# ADCMP.net
KiCad netlist of a schematic drawn in Altium Designer
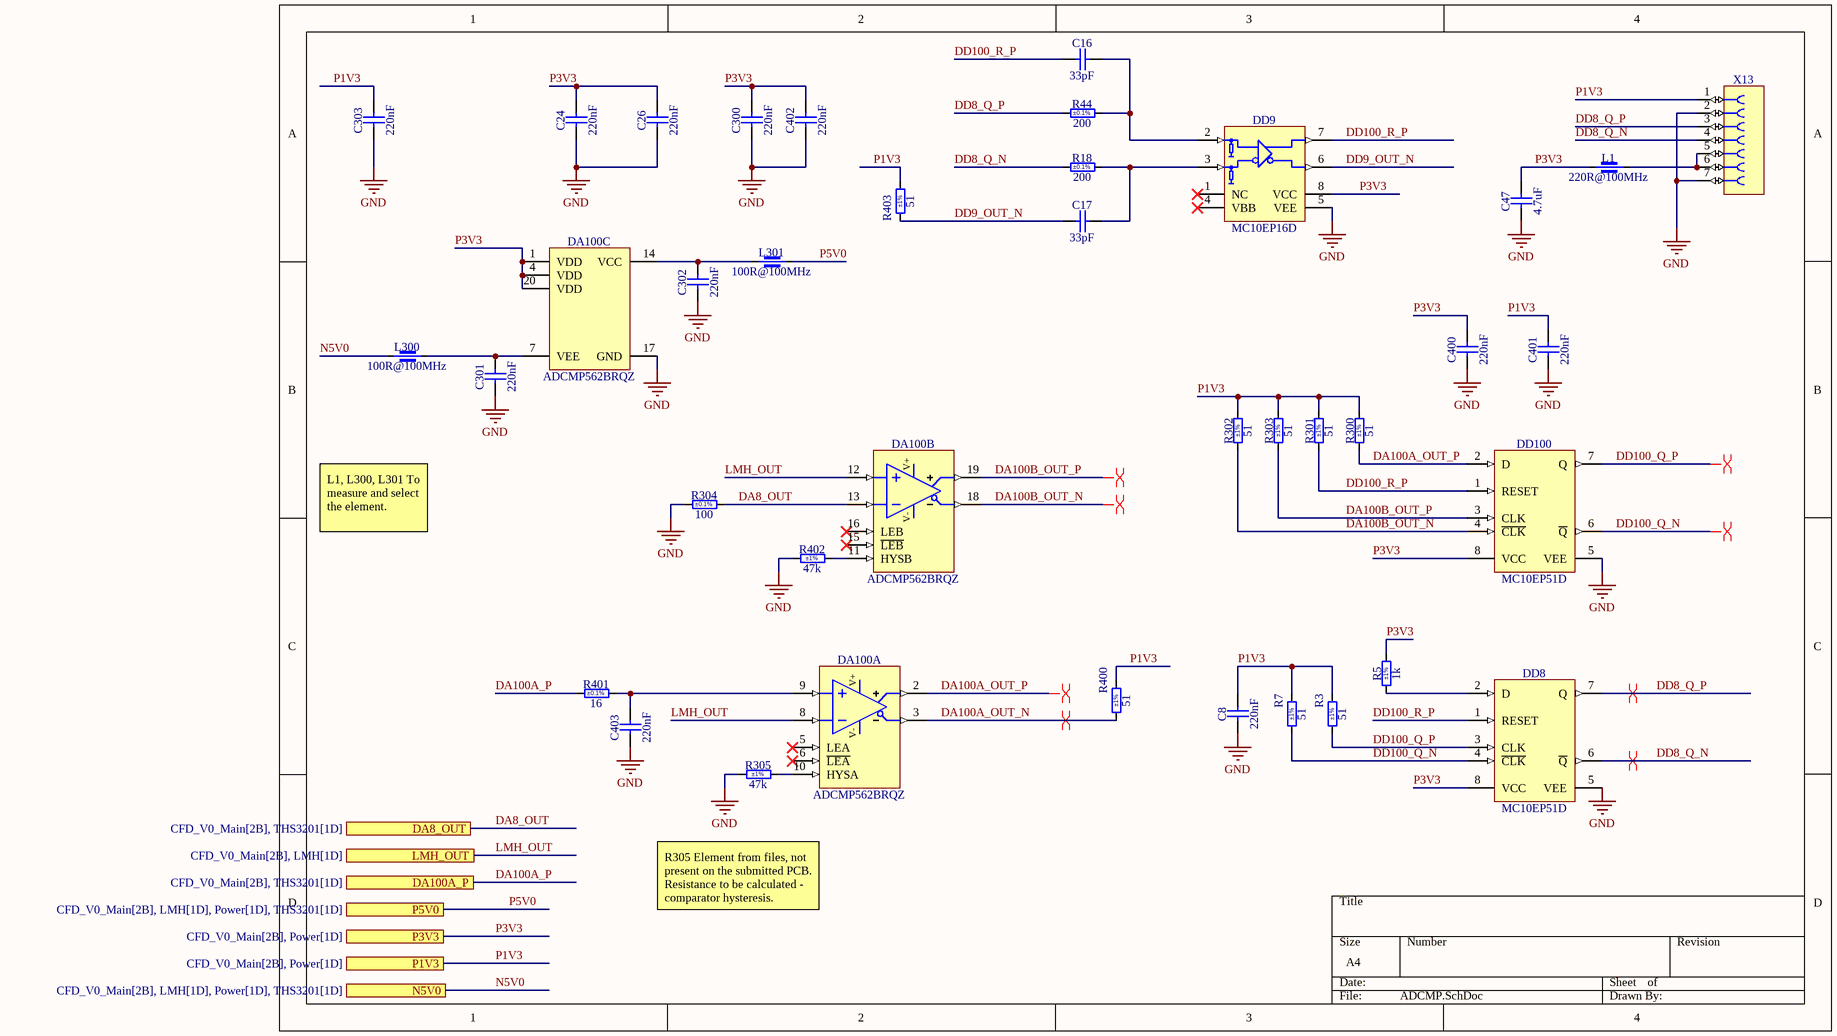
[diagram p0: ADCMP.SchDoc]

(export (version "E")
  (design (tool "Eeschema 10.0.6"))
  (components
    (comp (ref "C8")
      (value "220nF")
      (footprint "CAPC2012X135N")
      (description "Non-polarised capacitor")
      (fields
        (field (name "PART NUMBER") "CC0805_220NF_50V_10%_X7R")
        (field (name "VOLTAGE") "50V")
        (field (name "AUTHOR") "CERN DEM JLC")
      )
      (libsource (lib "Capacitors") (part "Capacitor - non polarized"))
    )
    (comp (ref "C16")
      (value "33pF")
      (footprint "CAPC2012X135N")
      (description "Non-polarised capacitor")
      (fields
        (field (name "PART NUMBER") "CC0805_33PF_50V_5%_NP0")
        (field (name "VOLTAGE") "50V")
        (field (name "AUTHOR") "CERN DEM JLC")
      )
      (libsource (lib "Capacitors") (part "Capacitor - non polarized"))
    )
    (comp (ref "C17")
      (value "33pF")
      (footprint "CAPC2012X135N")
      (description "Non-polarised capacitor")
      (fields
        (field (name "PART NUMBER") "CC0805_33PF_50V_5%_NP0")
        (field (name "VOLTAGE") "50V")
        (field (name "AUTHOR") "CERN DEM JLC")
      )
      (libsource (lib "Capacitors") (part "Capacitor - non polarized"))
    )
    (comp (ref "C24")
      (value "220nF")
      (footprint "CAPC2012X135N")
      (description "Non-polarised capacitor")
      (fields
        (field (name "PART NUMBER") "CC0805_220NF_50V_10%_X7R")
        (field (name "VOLTAGE") "50V")
        (field (name "AUTHOR") "CERN DEM JLC")
      )
      (libsource (lib "Capacitors") (part "Capacitor - non polarized"))
    )
    (comp (ref "C26")
      (value "220nF")
      (footprint "CAPC2012X135N")
      (description "Non-polarised capacitor")
      (fields
        (field (name "PART NUMBER") "CC0805_220NF_50V_10%_X7R")
        (field (name "VOLTAGE") "50V")
        (field (name "AUTHOR") "CERN DEM JLC")
      )
      (libsource (lib "Capacitors") (part "Capacitor - non polarized"))
    )
    (comp (ref "C47")
      (value "4.7uF")
      (footprint "CAPC3216X180N")
      (description "Non-polarised capacitor")
      (fields
        (field (name "PART NUMBER") "CC1206_4.7UF_25V_10%_X7R")
        (field (name "VOLTAGE") "25V")
        (field (name "AUTHOR") "CERN DEM WB")
      )
      (libsource (lib "Capacitors") (part "Capacitor - non polarized"))
    )
    (comp (ref "C300")
      (value "220nF")
      (footprint "CAPC1608X87N")
      (description "Non-polarised capacitor")
      (fields
        (field (name "PART NUMBER") "CC0603_220NF_25V_10%_X7R")
        (field (name "VOLTAGE") "25V")
        (field (name "AUTHOR") "CERN DEM JLC")
      )
      (libsource (lib "Capacitors") (part "Capacitor - non polarized"))
    )
    (comp (ref "C301")
      (value "220nF")
      (footprint "CAPC1608X87N")
      (description "Non-polarised capacitor")
      (fields
        (field (name "PART NUMBER") "CC0603_220NF_25V_10%_X7R")
        (field (name "VOLTAGE") "25V")
        (field (name "AUTHOR") "CERN DEM JLC")
      )
      (libsource (lib "Capacitors") (part "Capacitor - non polarized"))
    )
    (comp (ref "C302")
      (value "220nF")
      (footprint "CAPC1608X87N")
      (description "Non-polarised capacitor")
      (fields
        (field (name "PART NUMBER") "CC0603_220NF_25V_10%_X7R")
        (field (name "VOLTAGE") "25V")
        (field (name "AUTHOR") "CERN DEM JLC")
      )
      (libsource (lib "Capacitors") (part "Capacitor - non polarized"))
    )
    (comp (ref "C303")
      (value "220nF")
      (footprint "CAPC2012X135N")
      (description "Non-polarised capacitor")
      (fields
        (field (name "PART NUMBER") "CC0805_220NF_50V_10%_X7R")
        (field (name "VOLTAGE") "50V")
        (field (name "AUTHOR") "CERN DEM JLC")
      )
      (libsource (lib "Capacitors") (part "Capacitor - non polarized"))
    )
    (comp (ref "C400")
      (value "220nF")
      (footprint "CAPC2012X135N")
      (description "Non-polarised capacitor")
      (fields
        (field (name "PART NUMBER") "CC0805_220NF_50V_10%_X7R")
        (field (name "VOLTAGE") "50V")
        (field (name "AUTHOR") "CERN DEM JLC")
      )
      (libsource (lib "Capacitors") (part "Capacitor - non polarized"))
    )
    (comp (ref "C401")
      (value "220nF")
      (footprint "CAPC2012X135N")
      (description "Non-polarised capacitor")
      (fields
        (field (name "PART NUMBER") "CC0805_220NF_50V_10%_X7R")
        (field (name "VOLTAGE") "50V")
        (field (name "AUTHOR") "CERN DEM JLC")
      )
      (libsource (lib "Capacitors") (part "Capacitor - non polarized"))
    )
    (comp (ref "C402")
      (value "220nF")
      (footprint "CAPC1608X87N")
      (description "Non-polarised capacitor")
      (fields
        (field (name "PART NUMBER") "CC0603_220NF_25V_10%_X7R")
        (field (name "VOLTAGE") "25V")
        (field (name "AUTHOR") "CERN DEM JLC")
      )
      (libsource (lib "Capacitors") (part "Capacitor - non polarized"))
    )
    (comp (ref "C403")
      (value "220nF")
      (footprint "CAPC1608X87N")
      (description "Non-polarised capacitor")
      (fields
        (field (name "PART NUMBER") "CC0603_220NF_25V_10%_X7R")
        (field (name "VOLTAGE") "25V")
        (field (name "AUTHOR") "CERN DEM JLC")
      )
      (libsource (lib "Capacitors") (part "Capacitor - non polarized"))
    )
    (comp (ref "DA100")
      (value "ADCMP562BRQZ")
      (footprint "SOP63P600X175-20AN")
      (description "Dual, High Speed PECL Comparators")
      (fields
        (field (name "MANUFACTURER") "ANALOG DEVICES")
        (field (name "MANUFACTURER PART NUMBER") "ADCMP562BRQ")
        (field (name "AUTHOR") "CERN DEM MR")
      )
      (libsource (lib "ICs And Semiconductors") (part "ADCMP562BRQZ"))
    )
    (comp (ref "DD8")
      (value "MC10EP51D")
      (footprint "SOIC127P600X175-8N")
      (description "3.3V/5V ECL D Flip-Flop with Reset and Differential Clock")
      (fields (field (name "MANUFACTURER") "ON SEMICONDUCTOR") (field (name "AUTHOR") "CERN DEM HF"))
      (libsource (lib "ICs And Semiconductors") (part "10EP51"))
    )
    (comp (ref "DD9")
      (value "MC10EP16D")
      (footprint "SOIC127P600X175-8N")
      (description "3.3V / 5V ECL Differential Receiver/Driver")
      (fields (field (name "MANUFACTURER") "ON SEMICONDUCTOR") (field (name "AUTHOR") "CERN DEM HF"))
      (libsource (lib "ICs And Semiconductors") (part "10EP16"))
    )
    (comp (ref "DD100")
      (value "MC10EP51D")
      (footprint "SOIC127P600X175-8N")
      (description "3.3V/5V ECL D Flip-Flop with Reset and Differential Clock")
      (fields (field (name "MANUFACTURER") "ON SEMICONDUCTOR") (field (name "AUTHOR") "CERN DEM HF"))
      (libsource (lib "ICs And Semiconductors") (part "10EP51"))
    )
    (comp (ref "L1")
      (value "220R@100MHz")
      (footprint "INDC2012X105N")
      (fields
        (field (name "PART NUMBER") "IND0805_TDK_MPZ2012S221A")
        (field (name "POWER") "3A")
        (field (name "TOLERANCE") "±25%")
        (field (name "AUTHOR") "CERN DEM HF")
      )
      (libsource (lib "Inductors & Transformers") (part "Ferrite Bead"))
    )
    (comp (ref "L300")
      (value "100R@100MHz")
      (footprint "INDC1608X75N")
      (fields
        (field (name "PART NUMBER") "IND0603_TDK_MPZ1608S101ATAH0")
        (field (name "POWER") "3A")
        (field (name "TOLERANCE") "±25%")
        (field (name "AUTHOR") "CERN DEM JMW")
      )
      (libsource (lib "Inductors & Transformers") (part "Ferrite Bead"))
    )
    (comp (ref "L301")
      (value "100R@100MHz")
      (footprint "INDC1608X75N")
      (fields
        (field (name "PART NUMBER") "IND0603_TDK_MPZ1608S101ATAH0")
        (field (name "POWER") "3A")
        (field (name "TOLERANCE") "±25%")
        (field (name "AUTHOR") "CERN DEM JMW")
      )
      (libsource (lib "Inductors & Transformers") (part "Ferrite Bead"))
    )
    (comp (ref "R3")
      (value "51")
      (footprint "RESC2012X60N")
      (description "Resistor - 1%")
      (fields
        (field (name "TOLERANCE") "±1%")
        (field (name "PART NUMBER") "R0805_51R_1%_0.125W_100PPM")
        (field (name "POWER") "0.125W")
        (field (name "AUTHOR") "CERN DEM JLC")
      )
      (libsource (lib "Resistors") (part "Resistor - 1%"))
    )
    (comp (ref "R5")
      (value "1k")
      (footprint "RESC2012X60N")
      (description "Resistor - 1%")
      (fields
        (field (name "TOLERANCE") "±1%")
        (field (name "PART NUMBER") "R0805_1K_1%_0.125W_100PPM")
        (field (name "POWER") "0.125W")
        (field (name "AUTHOR") "CERN DEM JLC")
      )
      (libsource (lib "Resistors") (part "Resistor - 1%"))
    )
    (comp (ref "R7")
      (value "51")
      (footprint "RESC2012X60N")
      (description "Resistor - 1%")
      (fields
        (field (name "TOLERANCE") "±1%")
        (field (name "PART NUMBER") "R0805_51R_1%_0.125W_100PPM")
        (field (name "POWER") "0.125W")
        (field (name "AUTHOR") "CERN DEM JLC")
      )
      (libsource (lib "Resistors") (part "Resistor - 1%"))
    )
    (comp (ref "R18")
      (value "200")
      (footprint "RESC2012X60N")
      (description "Resistor - 0.1%")
      (fields
        (field (name "TOLERANCE") "±0.1%")
        (field (name "PART NUMBER") "R0805_200R_0.1%_0.1W_10PPM")
        (field (name "POWER") "0.1W")
        (field (name "AUTHOR") "CERN DEM JLC")
      )
      (libsource (lib "Resistors") (part "Resistor - 0.1%"))
    )
    (comp (ref "R44")
      (value "200")
      (footprint "RESC2012X60N")
      (description "Resistor - 0.1%")
      (fields
        (field (name "TOLERANCE") "±0.1%")
        (field (name "PART NUMBER") "R0805_200R_0.1%_0.1W_10PPM")
        (field (name "POWER") "0.1W")
        (field (name "AUTHOR") "CERN DEM JLC")
      )
      (libsource (lib "Resistors") (part "Resistor - 0.1%"))
    )
    (comp (ref "R300")
      (value "51")
      (footprint "RESC2012X60N")
      (description "Resistor - 1%")
      (fields
        (field (name "TOLERANCE") "±1%")
        (field (name "PART NUMBER") "R0805_51R_1%_0.125W_100PPM")
        (field (name "POWER") "0.125W")
        (field (name "AUTHOR") "CERN DEM JLC")
      )
      (libsource (lib "Resistors") (part "Resistor - 1%"))
    )
    (comp (ref "R301")
      (value "51")
      (footprint "RESC2012X60N")
      (description "Resistor - 1%")
      (fields
        (field (name "TOLERANCE") "±1%")
        (field (name "PART NUMBER") "R0805_51R_1%_0.125W_100PPM")
        (field (name "POWER") "0.125W")
        (field (name "AUTHOR") "CERN DEM JLC")
      )
      (libsource (lib "Resistors") (part "Resistor - 1%"))
    )
    (comp (ref "R302")
      (value "51")
      (footprint "RESC2012X60N")
      (description "Resistor - 1%")
      (fields
        (field (name "TOLERANCE") "±1%")
        (field (name "PART NUMBER") "R0805_51R_1%_0.125W_100PPM")
        (field (name "POWER") "0.125W")
        (field (name "AUTHOR") "CERN DEM JLC")
      )
      (libsource (lib "Resistors") (part "Resistor - 1%"))
    )
    (comp (ref "R303")
      (value "51")
      (footprint "RESC2012X60N")
      (description "Resistor - 1%")
      (fields
        (field (name "TOLERANCE") "±1%")
        (field (name "PART NUMBER") "R0805_51R_1%_0.125W_100PPM")
        (field (name "POWER") "0.125W")
        (field (name "AUTHOR") "CERN DEM JLC")
      )
      (libsource (lib "Resistors") (part "Resistor - 1%"))
    )
    (comp (ref "R304")
      (value "100")
      (footprint "RESC1608X55N")
      (description "Resistor - 0.1%")
      (fields
        (field (name "TOLERANCE") "±0.1%")
        (field (name "PART NUMBER") "R0603_100R_0.1%_0.1W_10PPM_VISHAY_MCT")
        (field (name "POWER") "0.1W")
        (field (name "AUTHOR") "CERN DEM BC")
      )
      (libsource (lib "Resistors") (part "Resistor - 0.1%"))
    )
    (comp (ref "R305")
      (value "47k")
      (footprint "RESC1608X55N")
      (description "Resistor - 1%")
      (fields
        (field (name "TOLERANCE") "±1%")
        (field (name "PART NUMBER") "R0603_47K_1%_0.1W_100PPM")
        (field (name "POWER") "0.1W")
        (field (name "AUTHOR") "CERN DEM JLC")
      )
      (libsource (lib "Resistors") (part "Resistor - 1%"))
    )
    (comp (ref "R400")
      (value "51")
      (footprint "RESC2012X60N")
      (description "Resistor - 1%")
      (fields
        (field (name "TOLERANCE") "±1%")
        (field (name "PART NUMBER") "R0805_51R_1%_0.125W_100PPM")
        (field (name "POWER") "0.125W")
        (field (name "AUTHOR") "CERN DEM JLC")
      )
      (libsource (lib "Resistors") (part "Resistor - 1%"))
    )
    (comp (ref "R401")
      (value "16")
      (footprint "RESC1608X64N")
      (description "Resistor - 0.1%")
      (fields
        (field (name "TOLERANCE") "±0.1%")
        (field (name "PART NUMBER") "R0603_16R_0.1%_0.1W_10PPM")
        (field (name "POWER") "0.1W")
        (field (name "AUTHOR") "CERN DEM HF")
      )
      (libsource (lib "Resistors") (part "Resistor - 0.1%"))
    )
    (comp (ref "R402")
      (value "47k")
      (footprint "RESC1608X55N")
      (description "Resistor - 1%")
      (fields
        (field (name "TOLERANCE") "±1%")
        (field (name "PART NUMBER") "R0603_47K_1%_0.1W_100PPM")
        (field (name "POWER") "0.1W")
        (field (name "AUTHOR") "CERN DEM JLC")
      )
      (libsource (lib "Resistors") (part "Resistor - 1%"))
    )
    (comp (ref "R403")
      (value "51")
      (footprint "RESC2012X60N")
      (description "Resistor - 1%")
      (fields
        (field (name "TOLERANCE") "±1%")
        (field (name "PART NUMBER") "R0805_51R_1%_0.125W_100PPM")
        (field (name "POWER") "0.125W")
        (field (name "AUTHOR") "CERN DEM JLC")
      )
      (libsource (lib "Resistors") (part "Resistor - 1%"))
    )
    (comp (ref "X13")
      (value "Socket 7")
      (footprint "SAMTEC_CES-107-01-T-S")
      (description "Connector 7 Female")
      (fields
        (field (name "PART NUMBER") "SAMTEC_CES-107-01-L-S")
        (field (name "MANUFACTURER") "SAMTEC")
        (field (name "AUTHOR") "CERN DEM HF")
      )
      (libsource (lib "Connectors") (part "Connector 7 Female"))
    )
  )
  (nets
    (net (code "1") (name "/DA8_OUT") (class "Default")
      (node (ref "DA100") (pin "13") (pinfunction "-INB_13") (pintype "input"))
      (node (ref "R304") (pin "2") (pinfunction "2_2") (pintype "passive"))
    )
    (net (code "2") (name "/DA100A_OUT_N") (class "Default")
      (node (ref "DA100") (pin "3") (pinfunction "~{QA}_3") (pintype "output"))
      (node (ref "R400") (pin "1") (pinfunction "1_1") (pintype "passive"))
    )
    (net (code "3") (name "/DA100A_OUT_P") (class "Default")
      (node (ref "DA100") (pin "2") (pinfunction "QA_2") (pintype "output"))
      (node (ref "DD100") (pin "2") (pinfunction "D_2") (pintype "input"))
      (node (ref "R300") (pin "1") (pinfunction "1_1") (pintype "passive"))
    )
    (net (code "4") (name "/DA100A_P") (class "Default")
      (node (ref "R401") (pin "1") (pinfunction "1_1") (pintype "passive"))
    )
    (net (code "5") (name "/DA100B_OUT_N") (class "Default")
      (node (ref "DA100") (pin "18") (pinfunction "~{QB}_18") (pintype "output"))
      (node (ref "DD100") (pin "4") (pinfunction "~{CLK}_4") (pintype "input"))
      (node (ref "R302") (pin "1") (pinfunction "1_1") (pintype "passive"))
    )
    (net (code "6") (name "/DA100B_OUT_P") (class "Default")
      (node (ref "DA100") (pin "19") (pinfunction "QB_19") (pintype "output"))
      (node (ref "DD100") (pin "3") (pinfunction "CLK_3") (pintype "input"))
      (node (ref "R303") (pin "1") (pinfunction "1_1") (pintype "passive"))
    )
    (net (code "7") (name "/DD8_Q_N") (class "Default")
      (node (ref "DD8") (pin "6") (pinfunction "~{Q}_6") (pintype "output"))
      (node (ref "R18") (pin "1") (pinfunction "1_1") (pintype "passive"))
      (node (ref "X13") (pin "4") (pinfunction "4_4") (pintype "bidirectional"))
    )
    (net (code "8") (name "/DD8_Q_P") (class "Default")
      (node (ref "DD8") (pin "7") (pinfunction "Q_7") (pintype "output"))
      (node (ref "R44") (pin "1") (pinfunction "1_1") (pintype "passive"))
      (node (ref "X13") (pin "3") (pinfunction "3_3") (pintype "bidirectional"))
    )
    (net (code "9") (name "/DD9_OUT_N") (class "Default")
      (node (ref "C17") (pin "1") (pinfunction "1_1") (pintype "passive"))
      (node (ref "DD9") (pin "6") (pinfunction "~{Q}_6") (pintype "output"))
      (node (ref "R403") (pin "1") (pinfunction "1_1") (pintype "passive"))
    )
    (net (code "10") (name "/DD100_Q_N") (class "Default")
      (node (ref "DD100") (pin "6") (pinfunction "~{Q}_6") (pintype "output"))
      (node (ref "DD8") (pin "4") (pinfunction "~{CLK}_4") (pintype "input"))
      (node (ref "R7") (pin "1") (pinfunction "1_1") (pintype "passive"))
    )
    (net (code "11") (name "/DD100_Q_P") (class "Default")
      (node (ref "DD100") (pin "7") (pinfunction "Q_7") (pintype "output"))
      (node (ref "DD8") (pin "3") (pinfunction "CLK_3") (pintype "input"))
      (node (ref "R3") (pin "1") (pinfunction "1_1") (pintype "passive"))
    )
    (net (code "12") (name "/DD100_R_P") (class "Default")
      (node (ref "C16") (pin "1") (pinfunction "1_1") (pintype "passive"))
      (node (ref "DD100") (pin "1") (pinfunction "RESET_1") (pintype "input"))
      (node (ref "DD8") (pin "1") (pinfunction "RESET_1") (pintype "input"))
      (node (ref "DD9") (pin "7") (pinfunction "Q_7") (pintype "output"))
      (node (ref "R301") (pin "1") (pinfunction "1_1") (pintype "passive"))
    )
    (net (code "13") (name "/LMH_OUT") (class "Default")
      (node (ref "DA100") (pin "12") (pinfunction "+INB_12") (pintype "input"))
      (node (ref "DA100") (pin "8") (pinfunction "-INA_8") (pintype "input"))
    )
    (net (code "14") (name "/N5V0") (class "Default")
      (node (ref "L300") (pin "1") (pinfunction "1_1") (pintype "passive"))
    )
    (net (code "15") (name "/P1V3") (class "Default")
      (node (ref "C303") (pin "2") (pinfunction "2_2") (pintype "passive"))
      (node (ref "C401") (pin "2") (pinfunction "2_2") (pintype "passive"))
      (node (ref "C8") (pin "2") (pinfunction "2_2") (pintype "passive"))
      (node (ref "R3") (pin "2") (pinfunction "2_2") (pintype "passive"))
      (node (ref "R300") (pin "2") (pinfunction "2_2") (pintype "passive"))
      (node (ref "R301") (pin "2") (pinfunction "2_2") (pintype "passive"))
      (node (ref "R302") (pin "2") (pinfunction "2_2") (pintype "passive"))
      (node (ref "R303") (pin "2") (pinfunction "2_2") (pintype "passive"))
      (node (ref "R400") (pin "2") (pinfunction "2_2") (pintype "passive"))
      (node (ref "R403") (pin "2") (pinfunction "2_2") (pintype "passive"))
      (node (ref "R7") (pin "2") (pinfunction "2_2") (pintype "passive"))
      (node (ref "X13") (pin "1") (pinfunction "1_1") (pintype "bidirectional"))
    )
    (net (code "16") (name "/P3V3") (class "Default")
      (node (ref "C24") (pin "2") (pinfunction "2_2") (pintype "passive"))
      (node (ref "C26") (pin "2") (pinfunction "2_2") (pintype "passive"))
      (node (ref "C300") (pin "2") (pinfunction "2_2") (pintype "passive"))
      (node (ref "C400") (pin "2") (pinfunction "2_2") (pintype "passive"))
      (node (ref "C402") (pin "2") (pinfunction "2_2") (pintype "passive"))
      (node (ref "C47") (pin "2") (pinfunction "2_2") (pintype "passive"))
      (node (ref "DA100") (pin "1") (pinfunction "VDD_1") (pintype "power_in"))
      (node (ref "DA100") (pin "20") (pinfunction "VDD_20") (pintype "power_in"))
      (node (ref "DA100") (pin "4") (pinfunction "VDD_4") (pintype "power_in"))
      (node (ref "DD100") (pin "8") (pinfunction "VCC_8") (pintype "power_in"))
      (node (ref "DD8") (pin "8") (pinfunction "VCC_8") (pintype "power_in"))
      (node (ref "DD9") (pin "8") (pinfunction "VCC_8") (pintype "power_in"))
      (node (ref "L1") (pin "1") (pinfunction "1_1") (pintype "passive"))
      (node (ref "R5") (pin "2") (pinfunction "2_2") (pintype "passive"))
    )
    (net (code "17") (name "/P5V0") (class "Default")
      (node (ref "L301") (pin "2") (pinfunction "2_2") (pintype "passive"))
    )
    (net (code "18") (name "GND") (class "Default")
      (node (ref "C24") (pin "1") (pinfunction "1_1") (pintype "passive"))
      (node (ref "C26") (pin "1") (pinfunction "1_1") (pintype "passive"))
      (node (ref "C300") (pin "1") (pinfunction "1_1") (pintype "passive"))
      (node (ref "C301") (pin "1") (pinfunction "1_1") (pintype "passive"))
      (node (ref "C302") (pin "1") (pinfunction "1_1") (pintype "passive"))
      (node (ref "C303") (pin "1") (pinfunction "1_1") (pintype "passive"))
      (node (ref "C400") (pin "1") (pinfunction "1_1") (pintype "passive"))
      (node (ref "C401") (pin "1") (pinfunction "1_1") (pintype "passive"))
      (node (ref "C402") (pin "1") (pinfunction "1_1") (pintype "passive"))
      (node (ref "C403") (pin "1") (pinfunction "1_1") (pintype "passive"))
      (node (ref "C47") (pin "1") (pinfunction "1_1") (pintype "passive"))
      (node (ref "C8") (pin "1") (pinfunction "1_1") (pintype "passive"))
      (node (ref "DA100") (pin "17") (pinfunction "GND_17") (pintype "power_in"))
      (node (ref "DD100") (pin "5") (pinfunction "VEE_5") (pintype "power_in"))
      (node (ref "DD8") (pin "5") (pinfunction "VEE_5") (pintype "power_in"))
      (node (ref "DD9") (pin "5") (pinfunction "VEE_5") (pintype "power_in"))
      (node (ref "R304") (pin "1") (pinfunction "1_1") (pintype "passive"))
      (node (ref "R305") (pin "1") (pinfunction "1_1") (pintype "passive"))
      (node (ref "R402") (pin "1") (pinfunction "1_1") (pintype "passive"))
      (node (ref "X13") (pin "2") (pinfunction "2_2") (pintype "bidirectional"))
      (node (ref "X13") (pin "7") (pinfunction "7_7") (pintype "bidirectional"))
    )
    (net (code "19") (name "Net-(DA100A-+INA)") (class "Default")
      (node (ref "C403") (pin "2") (pinfunction "2_2") (pintype "passive"))
      (node (ref "DA100") (pin "9") (pinfunction "+INA_9") (pintype "input"))
      (node (ref "R401") (pin "2") (pinfunction "2_2") (pintype "passive"))
    )
    (net (code "20") (name "Net-(DA100A-HYSA)") (class "Default")
      (node (ref "DA100") (pin "10") (pinfunction "HYSA_10") (pintype "input"))
      (node (ref "R305") (pin "2") (pinfunction "2_2") (pintype "passive"))
    )
    (net (code "21") (name "Net-(DA100B-HYSB)") (class "Default")
      (node (ref "DA100") (pin "11") (pinfunction "HYSB_11") (pintype "input"))
      (node (ref "R402") (pin "2") (pinfunction "2_2") (pintype "passive"))
    )
    (net (code "22") (name "Net-(DA100C-VCC)") (class "Default")
      (node (ref "C302") (pin "2") (pinfunction "2_2") (pintype "passive"))
      (node (ref "DA100") (pin "14") (pinfunction "VCC_14") (pintype "power_in"))
      (node (ref "L301") (pin "1") (pinfunction "1_1") (pintype "passive"))
    )
    (net (code "23") (name "Net-(DA100C-VEE)") (class "Default")
      (node (ref "C301") (pin "2") (pinfunction "2_2") (pintype "passive"))
      (node (ref "DA100") (pin "7") (pinfunction "VEE_7") (pintype "power_in"))
      (node (ref "L300") (pin "2") (pinfunction "2_2") (pintype "passive"))
    )
    (net (code "24") (name "Net-(DD8-D)") (class "Default")
      (node (ref "DD8") (pin "2") (pinfunction "D_2") (pintype "input"))
      (node (ref "R5") (pin "1") (pinfunction "1_1") (pintype "passive"))
    )
    (net (code "25") (name "Net-(DD9-D0)") (class "Default")
      (node (ref "C16") (pin "2") (pinfunction "2_2") (pintype "passive"))
      (node (ref "DD9") (pin "2") (pinfunction "D0_2") (pintype "input"))
      (node (ref "R44") (pin "2") (pinfunction "2_2") (pintype "passive"))
    )
    (net (code "26") (name "Net-(DD9-~{D0})") (class "Default")
      (node (ref "C17") (pin "2") (pinfunction "2_2") (pintype "passive"))
      (node (ref "DD9") (pin "3") (pinfunction "~{D0}_3") (pintype "input"))
      (node (ref "R18") (pin "2") (pinfunction "2_2") (pintype "passive"))
    )
    (net (code "27") (name "Net-(L1-Pad2)") (class "Default")
      (node (ref "L1") (pin "2") (pinfunction "2_2") (pintype "passive"))
      (node (ref "X13") (pin "5") (pinfunction "5_5") (pintype "bidirectional"))
      (node (ref "X13") (pin "6") (pinfunction "6_6") (pintype "bidirectional"))
    )
    (net (code "28") (name "unconnected-(DA100A-LEA-Pad5)") (class "Default")
      (node (ref "DA100") (pin "5") (pinfunction "LEA_5") (pintype "input+no_connect"))
    )
    (net (code "29") (name "unconnected-(DA100A-~{LEA}-Pad6)") (class "Default")
      (node (ref "DA100") (pin "6") (pinfunction "~{LEA}_6") (pintype "input+no_connect"))
    )
    (net (code "30") (name "unconnected-(DA100B-LEB-Pad16)") (class "Default")
      (node (ref "DA100") (pin "16") (pinfunction "LEB_16") (pintype "input+no_connect"))
    )
    (net (code "31") (name "unconnected-(DA100B-~{LEB}-Pad15)") (class "Default")
      (node (ref "DA100") (pin "15") (pinfunction "~{LEB}_15") (pintype "input+no_connect"))
    )
    (net (code "32") (name "unconnected-(DD9-NC-Pad1)") (class "Default")
      (node (ref "DD9") (pin "1") (pinfunction "NC_1") (pintype "passive+no_connect"))
    )
    (net (code "33") (name "unconnected-(DD9-VBB-Pad4)") (class "Default")
      (node (ref "DD9") (pin "4") (pinfunction "VBB_4") (pintype "power_in+no_connect"))
    )
  )
)
